# old_main_board.net
KiCad netlist of a schematic drawn in EAGLE
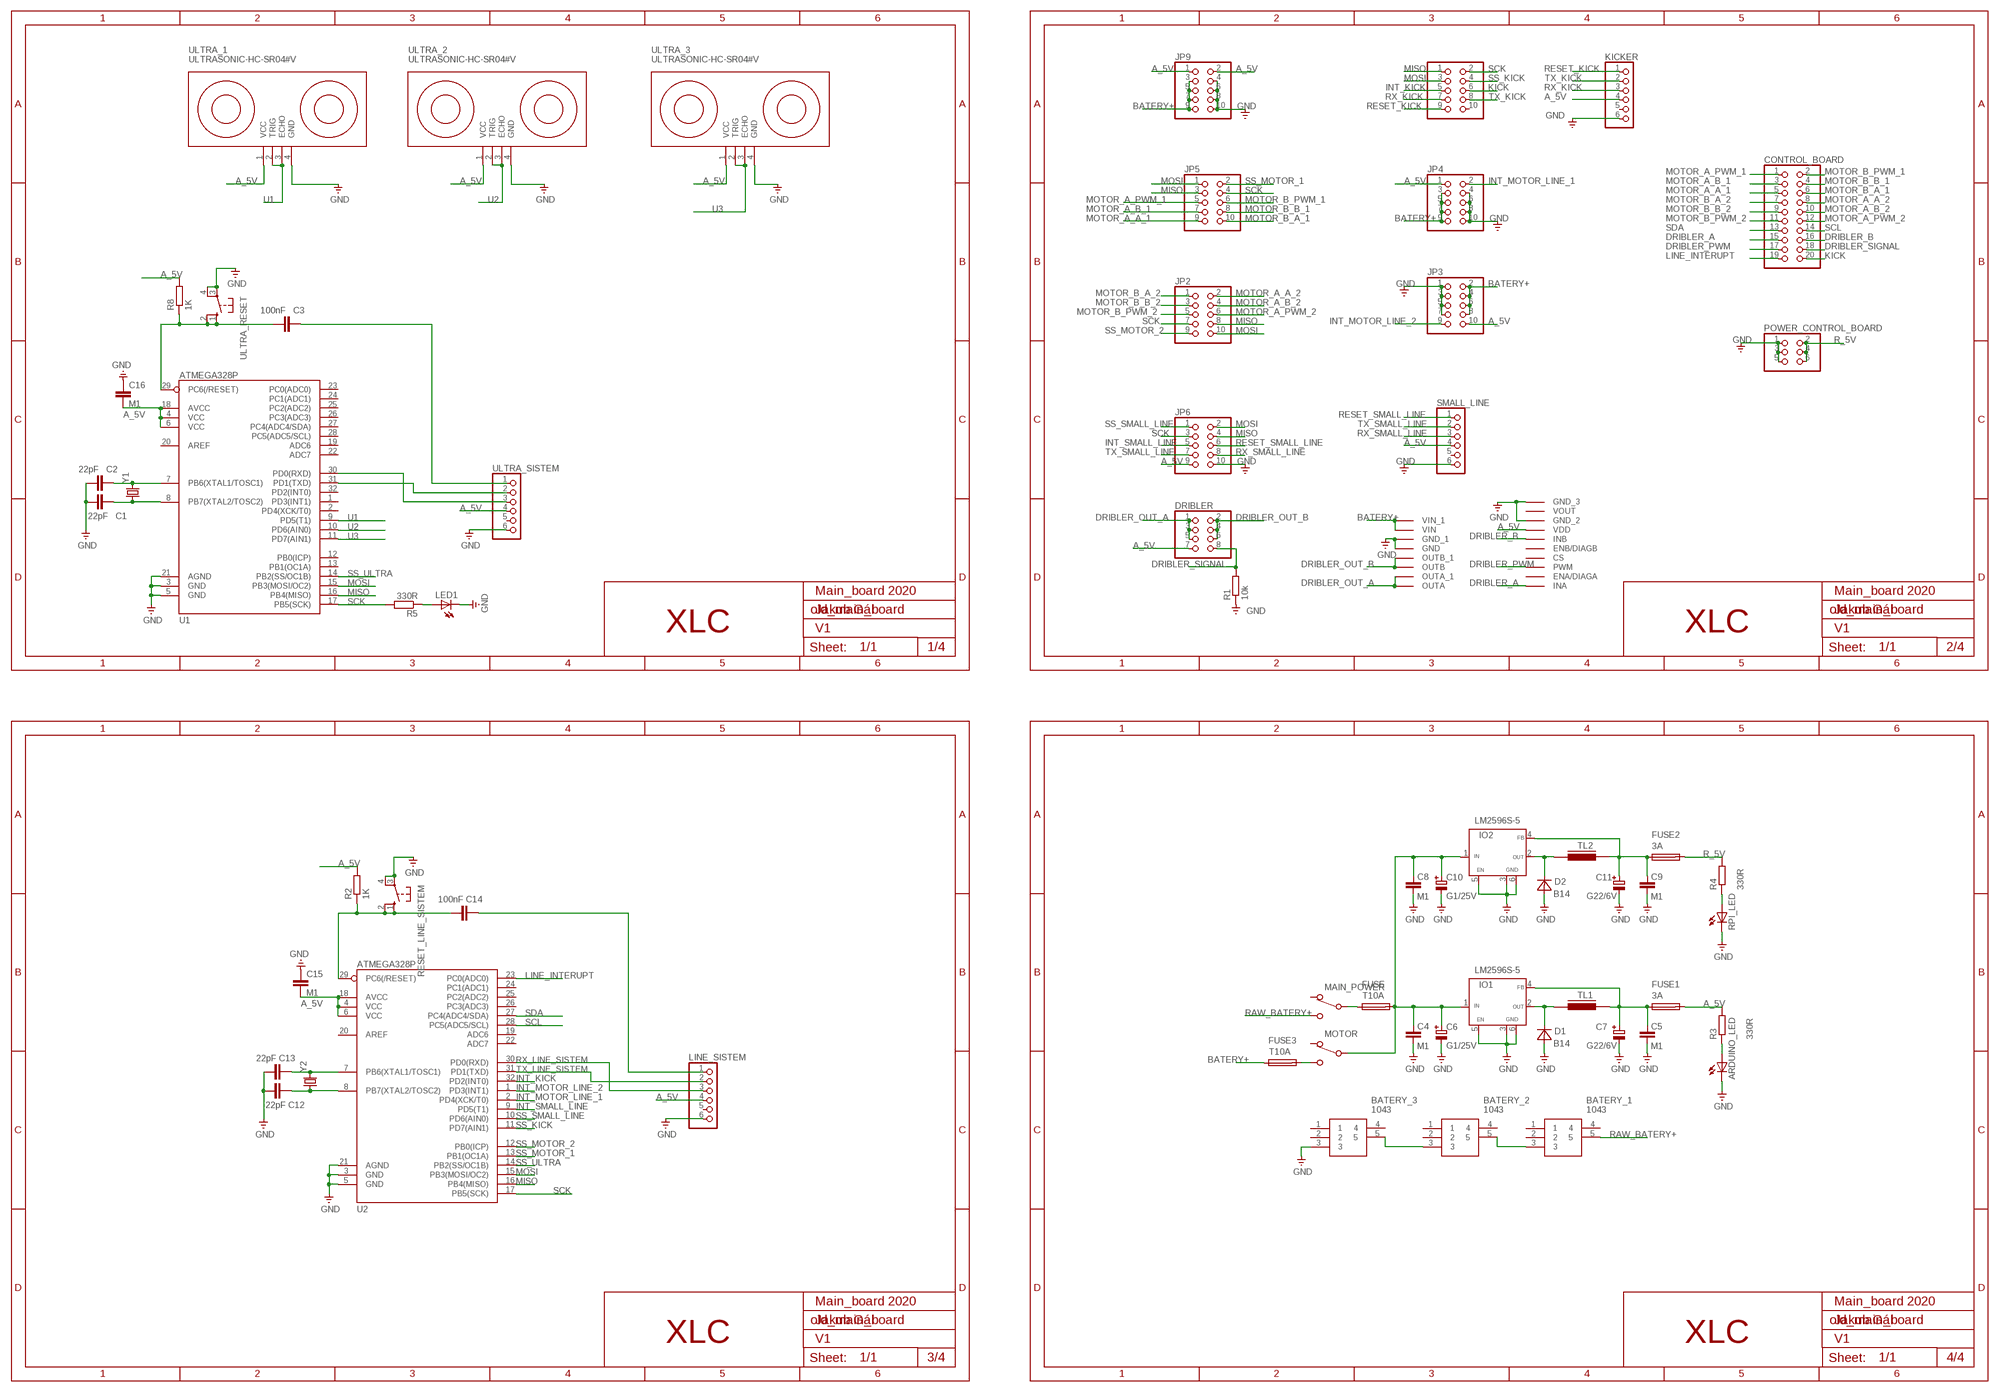
[diagram p0: schematic, sheet 1]

(export (version "E")
  (design (tool "Eeschema 10.0.6"))
  (components
    (comp (ref "ARDUINO_LED")
      (value "LEDCHIPLED_0603")
      (footprint "eagle-import:CHIPLED_0603")
      (libsource (lib "eagle-import") (part "LEDCHIPLED_0603"))
    )
    (comp (ref "BATERY_1")
      (value "1043")
      (footprint "eagle-import:1043")
      (fields (field (name "MOUSER_PART_NUMBER") "534-1043"))
      (libsource (lib "eagle-import") (part "1043"))
    )
    (comp (ref "BATERY_2")
      (value "1043")
      (footprint "eagle-import:1043")
      (fields (field (name "MOUSER_PART_NUMBER") "534-1043"))
      (libsource (lib "eagle-import") (part "1043"))
    )
    (comp (ref "BATERY_3")
      (value "1043")
      (footprint "eagle-import:1043")
      (fields (field (name "MOUSER_PART_NUMBER") "534-1043"))
      (libsource (lib "eagle-import") (part "1043"))
    )
    (comp (ref "C1")
      (value "22pF")
      (footprint "eagle-import:C0603")
      (libsource (lib "eagle-import") (part "rcl@1_C-EUC0603"))
    )
    (comp (ref "C2")
      (value "22pF")
      (footprint "eagle-import:C0603")
      (libsource (lib "eagle-import") (part "rcl@1_C-EUC0603"))
    )
    (comp (ref "C3")
      (value "100nF")
      (footprint "eagle-import:C0603")
      (libsource (lib "eagle-import") (part "rcl@1_C-EUC0603"))
    )
    (comp (ref "C4")
      (value "M1")
      (footprint "eagle-import:SMD-1206")
      (libsource (lib "eagle-import") (part "KOND-KERAM1206-SMD"))
    )
    (comp (ref "C5")
      (value "M1")
      (footprint "eagle-import:SMD-1206")
      (libsource (lib "eagle-import") (part "KOND-KERAM1206-SMD"))
    )
    (comp (ref "C6")
      (value "G1/25V")
      (footprint "eagle-import:SMD-ELE-D")
      (libsource (lib "eagle-import") (part "KOND-ELEKTD-SMD"))
    )
    (comp (ref "C7")
      (value "G22/6V")
      (footprint "eagle-import:SMD-ELE-D")
      (libsource (lib "eagle-import") (part "KOND-ELEKTD-SMD"))
    )
    (comp (ref "C8")
      (value "M1")
      (footprint "eagle-import:SMD-1206")
      (libsource (lib "eagle-import") (part "KOND-KERAM1206-SMD"))
    )
    (comp (ref "C9")
      (value "M1")
      (footprint "eagle-import:SMD-1206")
      (libsource (lib "eagle-import") (part "KOND-KERAM1206-SMD"))
    )
    (comp (ref "C10")
      (value "G1/25V")
      (footprint "eagle-import:SMD-ELE-D")
      (libsource (lib "eagle-import") (part "KOND-ELEKTD-SMD"))
    )
    (comp (ref "C11")
      (value "G22/6V")
      (footprint "eagle-import:SMD-ELE-D")
      (libsource (lib "eagle-import") (part "KOND-ELEKTD-SMD"))
    )
    (comp (ref "C12")
      (value "22pF")
      (footprint "eagle-import:C0603")
      (libsource (lib "eagle-import") (part "rcl@1_C-EUC0603"))
    )
    (comp (ref "C13")
      (value "22pF")
      (footprint "eagle-import:C0603")
      (libsource (lib "eagle-import") (part "rcl@1_C-EUC0603"))
    )
    (comp (ref "C14")
      (value "100nF")
      (footprint "eagle-import:C0603")
      (libsource (lib "eagle-import") (part "rcl@1_C-EUC0603"))
    )
    (comp (ref "C15")
      (value "M1")
      (footprint "eagle-import:C0603")
      (libsource (lib "eagle-import") (part "C-EUC0603"))
    )
    (comp (ref "C16")
      (value "M1")
      (footprint "eagle-import:C0603")
      (libsource (lib "eagle-import") (part "C-EUC0603"))
    )
    (comp (ref "CONTROL_BOARD")
      (value "PINHD-2X10_2.54-SMD")
      (footprint "eagle-import:2X10SMD")
      (libsource (lib "eagle-import") (part "PINHD-2X10_2.54-SMD"))
    )
    (comp (ref "D1")
      (value "B14")
      (footprint "eagle-import:D-3,6X5,5")
      (libsource (lib "eagle-import") (part "DIODASMD-3,6X5,5"))
    )
    (comp (ref "D2")
      (value "B14")
      (footprint "eagle-import:D-3,6X5,5")
      (libsource (lib "eagle-import") (part "DIODASMD-3,6X5,5"))
    )
    (comp (ref "DRIBLER")
      (value "PINHD-2X4_2.54-SMD")
      (footprint "eagle-import:2X04SMD")
      (libsource (lib "eagle-import") (part "PINHD-2X4_2.54-SMD"))
    )
    (comp (ref "FUSE")
      (value "T10A")
      (footprint "eagle-import:SH22,5A")
      (libsource (lib "eagle-import") (part "POISTKA2A"))
    )
    (comp (ref "FUSE1")
      (value "3A")
      (footprint "eagle-import:SH22,5A")
      (libsource (lib "eagle-import") (part "POISTKA2A"))
    )
    (comp (ref "FUSE2")
      (value "3A")
      (footprint "eagle-import:SH22,5A")
      (libsource (lib "eagle-import") (part "POISTKA2A"))
    )
    (comp (ref "FUSE3")
      (value "T10A")
      (footprint "eagle-import:SH22,5A")
      (libsource (lib "eagle-import") (part "POISTKA2A"))
    )
    (comp (ref "IO1")
      (value "LM2596S-5")
      (footprint "eagle-import:TO263-5")
      (libsource (lib "eagle-import") (part "LM2596S"))
    )
    (comp (ref "IO2")
      (value "LM2596S-5")
      (footprint "eagle-import:TO263-5")
      (libsource (lib "eagle-import") (part "LM2596S"))
    )
    (comp (ref "JP2")
      (value "PINHD-2X5_2.54-SMD")
      (footprint "eagle-import:2X05SMD")
      (libsource (lib "eagle-import") (part "PINHD-2X5_2.54-SMD"))
    )
    (comp (ref "JP3")
      (value "PINHD-2X5_2.54-SMD")
      (footprint "eagle-import:2X05SMD")
      (libsource (lib "eagle-import") (part "PINHD-2X5_2.54-SMD"))
    )
    (comp (ref "JP4")
      (value "PINHD-2X5_2.54-SMD")
      (footprint "eagle-import:2X05SMD")
      (libsource (lib "eagle-import") (part "PINHD-2X5_2.54-SMD"))
    )
    (comp (ref "JP5")
      (value "PINHD-2X5_2.54-SMD")
      (footprint "eagle-import:2X05SMD")
      (libsource (lib "eagle-import") (part "PINHD-2X5_2.54-SMD"))
    )
    (comp (ref "JP6")
      (value "PINHD-2X5_2.54-SMD")
      (footprint "eagle-import:2X05SMD")
      (libsource (lib "eagle-import") (part "PINHD-2X5_2.54-SMD"))
    )
    (comp (ref "JP8")
      (value "PINHD-2X5_2.54-SMD")
      (footprint "eagle-import:2X05SMD")
      (libsource (lib "eagle-import") (part "PINHD-2X5_2.54-SMD"))
    )
    (comp (ref "JP9")
      (value "PINHD-2X5_2.54-SMD")
      (footprint "eagle-import:2X05SMD")
      (libsource (lib "eagle-import") (part "PINHD-2X5_2.54-SMD"))
    )
    (comp (ref "KICKER")
      (value "PINHD-1X6")
      (footprint "eagle-import:1X06")
      (libsource (lib "eagle-import") (part "PINHD-1X6"))
    )
    (comp (ref "LED1")
      (value "LEDCHIPLED_0603")
      (footprint "eagle-import:CHIPLED_0603")
      (libsource (lib "eagle-import") (part "LEDCHIPLED_0603"))
    )
    (comp (ref "LINE_SISTEM")
      (value "PINHD-1X6")
      (footprint "eagle-import:1X06")
      (libsource (lib "eagle-import") (part "PINHD-1X6"))
    )
    (comp (ref "MAIN_POWER")
      (value "PREP-1PB")
      (footprint "eagle-import:P-B069B")
      (libsource (lib "eagle-import") (part "PREP-1PB"))
    )
    (comp (ref "MOTOR")
      (value "PREP-1PB")
      (footprint "eagle-import:P-B069B")
      (libsource (lib "eagle-import") (part "PREP-1PB"))
    )
    (comp (ref "POWER_CONTROL_BOARD")
      (value "PINHD-2X3_2.54-SMD")
      (footprint "eagle-import:2X03SMD")
      (libsource (lib "eagle-import") (part "PINHD-2X3_2.54-SMD"))
    )
    (comp (ref "R1")
      (value "10k")
      (footprint "eagle-import:R0603")
      (libsource (lib "eagle-import") (part "R-EU_R0603"))
    )
    (comp (ref "R2")
      (value "1K")
      (footprint "eagle-import:R0603")
      (libsource (lib "eagle-import") (part "R-EU_R0603"))
    )
    (comp (ref "R3")
      (value "330R")
      (footprint "eagle-import:R0603")
      (libsource (lib "eagle-import") (part "R-EU_R0603"))
    )
    (comp (ref "R4")
      (value "330R")
      (footprint "eagle-import:R0603")
      (libsource (lib "eagle-import") (part "R-EU_R0603"))
    )
    (comp (ref "R5")
      (value "330R")
      (footprint "eagle-import:R0603")
      (libsource (lib "eagle-import") (part "R-EU_R0603"))
    )
    (comp (ref "R8")
      (value "1K")
      (footprint "eagle-import:R0603")
      (libsource (lib "eagle-import") (part "R-EU_R0603"))
    )
    (comp (ref "RESET_LINE_SISTEM")
      (value "10-XX")
      (footprint "eagle-import:B3F-10XX")
      (fields (field (name "MPN") "B3F-1000"))
      (libsource (lib "eagle-import") (part "10-XX"))
    )
    (comp (ref "RPI_LED")
      (value "LEDCHIPLED_0603")
      (footprint "eagle-import:CHIPLED_0603")
      (libsource (lib "eagle-import") (part "LEDCHIPLED_0603"))
    )
    (comp (ref "SMALL_LINE")
      (value "PINHD-1X6")
      (footprint "eagle-import:1X06")
      (libsource (lib "eagle-import") (part "PINHD-1X6"))
    )
    (comp (ref "TL1")
      (value "INDUK-TLSMD1")
      (footprint "eagle-import:INDUK-TL")
      (libsource (lib "eagle-import") (part "INDUK-TLSMD1"))
    )
    (comp (ref "TL2")
      (value "INDUK-TLSMD1")
      (footprint "eagle-import:INDUK-TL")
      (libsource (lib "eagle-import") (part "INDUK-TLSMD1"))
    )
    (comp (ref "U$4")
      (value "MOTOR_DRIVER")
      (footprint "eagle-import:MOTOR_DRIVER")
      (libsource (lib "eagle-import") (part "MOTOR_DRIVER"))
    )
    (comp (ref "U1")
      (value "ATMEGA328P")
      (footprint "eagle-import:TQFP32-08")
      (libsource (lib "eagle-import") (part "ATMEGA328_SMT"))
    )
    (comp (ref "U2")
      (value "ATMEGA328P")
      (footprint "eagle-import:TQFP32-08")
      (libsource (lib "eagle-import") (part "ATMEGA328_SMT"))
    )
    (comp (ref "ULTRA_1")
      (value "ULTRASONIC-HC-SR04#V")
      (footprint "eagle-import:ULTRASONIC-HC-SR04#V")
      (libsource (lib "eagle-import") (part "ULTRASONIC-HC-SR04#V"))
    )
    (comp (ref "ULTRA_2")
      (value "ULTRASONIC-HC-SR04#V")
      (footprint "eagle-import:ULTRASONIC-HC-SR04#V")
      (libsource (lib "eagle-import") (part "ULTRASONIC-HC-SR04#V"))
    )
    (comp (ref "ULTRA_3")
      (value "ULTRASONIC-HC-SR04#V")
      (footprint "eagle-import:ULTRASONIC-HC-SR04#V")
      (libsource (lib "eagle-import") (part "ULTRASONIC-HC-SR04#V"))
    )
    (comp (ref "ULTRA_RESET")
      (value "10-XX")
      (footprint "eagle-import:B3F-10XX")
      (fields (field (name "MPN") "B3F-1000"))
      (libsource (lib "eagle-import") (part "10-XX"))
    )
    (comp (ref "ULTRA_SISTEM")
      (value "PINHD-1X6")
      (footprint "eagle-import:1X06")
      (libsource (lib "eagle-import") (part "PINHD-1X6"))
    )
    (comp (ref "Y1")
      (value "CRYSTALHC49US")
      (footprint "eagle-import:HC49US")
      (libsource (lib "eagle-import") (part "CRYSTALHC49US"))
    )
    (comp (ref "Y2")
      (value "CRYSTALHC49US")
      (footprint "eagle-import:HC49US")
      (libsource (lib "eagle-import") (part "CRYSTALHC49US"))
    )
  )
  (nets
    (net (code "1") (name "/A_5V") (class "Default")
      (node (ref "C15") (pin "2") (pinfunction "2_2") (pintype "passive"))
      (node (ref "C16") (pin "2") (pinfunction "2_2") (pintype "passive"))
      (node (ref "DRIBLER") (pin "7") (pinfunction "7_7") (pintype "passive"))
      (node (ref "FUSE1") (pin "2") (pinfunction "2_2") (pintype "passive"))
      (node (ref "JP3") (pin "10") (pinfunction "10_10") (pintype "passive"))
      (node (ref "JP4") (pin "1") (pinfunction "1_1") (pintype "passive"))
      (node (ref "JP6") (pin "9") (pinfunction "9_9") (pintype "passive"))
      (node (ref "JP9") (pin "1") (pinfunction "1_1") (pintype "passive"))
      (node (ref "JP9") (pin "2") (pinfunction "2_2") (pintype "passive"))
      (node (ref "KICKER") (pin "4") (pinfunction "4_4") (pintype "passive"))
      (node (ref "LINE_SISTEM") (pin "4") (pinfunction "4_4") (pintype "passive"))
      (node (ref "R2") (pin "2") (pinfunction "2_2") (pintype "passive"))
      (node (ref "R3") (pin "2") (pinfunction "2_2") (pintype "passive"))
      (node (ref "R8") (pin "2") (pinfunction "2_2") (pintype "passive"))
      (node (ref "SMALL_LINE") (pin "4") (pinfunction "4_4") (pintype "passive"))
      (node (ref "U$4") (pin "VDD") (pinfunction "VDD_VDD") (pintype "bidirectional"))
      (node (ref "U1") (pin "18") (pinfunction "AVCC_18") (pintype "bidirectional"))
      (node (ref "U1") (pin "4") (pinfunction "VCC_4") (pintype "bidirectional"))
      (node (ref "U1") (pin "6") (pinfunction "VCC_6") (pintype "bidirectional"))
      (node (ref "U2") (pin "18") (pinfunction "AVCC_18") (pintype "bidirectional"))
      (node (ref "U2") (pin "4") (pinfunction "VCC_4") (pintype "bidirectional"))
      (node (ref "U2") (pin "6") (pinfunction "VCC_6") (pintype "bidirectional"))
      (node (ref "ULTRA_1") (pin "1") (pinfunction "VCC_1") (pintype "power_in"))
      (node (ref "ULTRA_2") (pin "1") (pinfunction "VCC_1") (pintype "power_in"))
      (node (ref "ULTRA_3") (pin "1") (pinfunction "VCC_1") (pintype "power_in"))
      (node (ref "ULTRA_SISTEM") (pin "4") (pinfunction "4_4") (pintype "passive"))
    )
    (net (code "2") (name "/BATERY+") (class "Default")
      (node (ref "FUSE3") (pin "1") (pinfunction "1_1") (pintype "passive"))
      (node (ref "JP3") (pin "2") (pinfunction "2_2") (pintype "passive"))
      (node (ref "JP3") (pin "4") (pinfunction "4_4") (pintype "passive"))
      (node (ref "JP3") (pin "6") (pinfunction "6_6") (pintype "passive"))
      (node (ref "JP3") (pin "8") (pinfunction "8_8") (pintype "passive"))
      (node (ref "JP4") (pin "3") (pinfunction "3_3") (pintype "passive"))
      (node (ref "JP4") (pin "5") (pinfunction "5_5") (pintype "passive"))
      (node (ref "JP4") (pin "7") (pinfunction "7_7") (pintype "passive"))
      (node (ref "JP4") (pin "9") (pinfunction "9_9") (pintype "passive"))
      (node (ref "JP9") (pin "3") (pinfunction "3_3") (pintype "passive"))
      (node (ref "JP9") (pin "5") (pinfunction "5_5") (pintype "passive"))
      (node (ref "JP9") (pin "7") (pinfunction "7_7") (pintype "passive"))
      (node (ref "JP9") (pin "9") (pinfunction "9_9") (pintype "passive"))
      (node (ref "U$4") (pin "VIN") (pinfunction "VIN_VIN") (pintype "bidirectional"))
      (node (ref "U$4") (pin "VIN_1") (pinfunction "VIN_1_VIN_1") (pintype "bidirectional"))
    )
    (net (code "3") (name "/DRIBLER_A") (class "Default")
      (node (ref "CONTROL_BOARD") (pin "15") (pinfunction "15_15") (pintype "passive"))
      (node (ref "U$4") (pin "INA") (pinfunction "INA_INA") (pintype "bidirectional"))
    )
    (net (code "4") (name "/DRIBLER_B") (class "Default")
      (node (ref "CONTROL_BOARD") (pin "16") (pinfunction "16_16") (pintype "passive"))
      (node (ref "U$4") (pin "INB") (pinfunction "INB_INB") (pintype "bidirectional"))
    )
    (net (code "5") (name "/DRIBLER_OUT_A") (class "Default")
      (node (ref "DRIBLER") (pin "1") (pinfunction "1_1") (pintype "passive"))
      (node (ref "DRIBLER") (pin "3") (pinfunction "3_3") (pintype "passive"))
      (node (ref "DRIBLER") (pin "5") (pinfunction "5_5") (pintype "passive"))
      (node (ref "U$4") (pin "OUTA") (pinfunction "OUTA_OUTA") (pintype "bidirectional"))
      (node (ref "U$4") (pin "OUTA_1") (pinfunction "OUTA_1_OUTA_1") (pintype "bidirectional"))
    )
    (net (code "6") (name "/DRIBLER_OUT_B") (class "Default")
      (node (ref "DRIBLER") (pin "2") (pinfunction "2_2") (pintype "passive"))
      (node (ref "DRIBLER") (pin "4") (pinfunction "4_4") (pintype "passive"))
      (node (ref "DRIBLER") (pin "6") (pinfunction "6_6") (pintype "passive"))
      (node (ref "U$4") (pin "OUTB") (pinfunction "OUTB_OUTB") (pintype "bidirectional"))
      (node (ref "U$4") (pin "OUTB_1") (pinfunction "OUTB_1_OUTB_1") (pintype "bidirectional"))
    )
    (net (code "7") (name "/DRIBLER_PWM") (class "Default")
      (node (ref "CONTROL_BOARD") (pin "17") (pinfunction "17_17") (pintype "passive"))
      (node (ref "U$4") (pin "PWM") (pinfunction "PWM_PWM") (pintype "bidirectional"))
    )
    (net (code "8") (name "/DRIBLER_SIGNAL") (class "Default")
      (node (ref "CONTROL_BOARD") (pin "18") (pinfunction "18_18") (pintype "passive"))
      (node (ref "DRIBLER") (pin "8") (pinfunction "8_8") (pintype "passive"))
      (node (ref "R1") (pin "2") (pinfunction "2_2") (pintype "passive"))
    )
    (net (code "9") (name "/INT_KICK") (class "Default")
      (node (ref "JP8") (pin "5") (pinfunction "5_5") (pintype "passive"))
      (node (ref "U2") (pin "32") (pinfunction "PD2(INT0)_32") (pintype "bidirectional"))
    )
    (net (code "10") (name "/INT_MOTOR_LINE_1") (class "Default")
      (node (ref "JP4") (pin "2") (pinfunction "2_2") (pintype "passive"))
      (node (ref "U2") (pin "2") (pinfunction "PD4(XCK/T0)_2") (pintype "bidirectional"))
    )
    (net (code "11") (name "/INT_MOTOR_LINE_2") (class "Default")
      (node (ref "JP3") (pin "9") (pinfunction "9_9") (pintype "passive"))
      (node (ref "U2") (pin "1") (pinfunction "PD3(INT1)_1") (pintype "bidirectional"))
    )
    (net (code "12") (name "/INT_SMALL_LINE") (class "Default")
      (node (ref "JP6") (pin "5") (pinfunction "5_5") (pintype "passive"))
      (node (ref "U2") (pin "9") (pinfunction "PD5(T1)_9") (pintype "bidirectional"))
    )
    (net (code "13") (name "/KICK") (class "Default")
      (node (ref "CONTROL_BOARD") (pin "20") (pinfunction "20_20") (pintype "passive"))
      (node (ref "JP8") (pin "6") (pinfunction "6_6") (pintype "passive"))
    )
    (net (code "14") (name "/LINE_INTERUPT") (class "Default")
      (node (ref "CONTROL_BOARD") (pin "19") (pinfunction "19_19") (pintype "passive"))
      (node (ref "U2") (pin "23") (pinfunction "PC0(ADC0)_23") (pintype "bidirectional"))
    )
    (net (code "15") (name "/MISO") (class "Default")
      (node (ref "JP2") (pin "8") (pinfunction "8_8") (pintype "passive"))
      (node (ref "JP5") (pin "3") (pinfunction "3_3") (pintype "passive"))
      (node (ref "JP6") (pin "4") (pinfunction "4_4") (pintype "passive"))
      (node (ref "JP8") (pin "1") (pinfunction "1_1") (pintype "passive"))
      (node (ref "U1") (pin "16") (pinfunction "PB4(MISO)_16") (pintype "bidirectional"))
      (node (ref "U2") (pin "16") (pinfunction "PB4(MISO)_16") (pintype "bidirectional"))
    )
    (net (code "16") (name "/MOSI") (class "Default")
      (node (ref "JP2") (pin "10") (pinfunction "10_10") (pintype "passive"))
      (node (ref "JP5") (pin "1") (pinfunction "1_1") (pintype "passive"))
      (node (ref "JP6") (pin "2") (pinfunction "2_2") (pintype "passive"))
      (node (ref "JP8") (pin "3") (pinfunction "3_3") (pintype "passive"))
      (node (ref "U1") (pin "15") (pinfunction "PB3(MOSI/OC2)_15") (pintype "bidirectional"))
      (node (ref "U2") (pin "15") (pinfunction "PB3(MOSI/OC2)_15") (pintype "bidirectional"))
    )
    (net (code "17") (name "/MOTOR_A_A_1") (class "Default")
      (node (ref "CONTROL_BOARD") (pin "5") (pinfunction "5_5") (pintype "passive"))
      (node (ref "JP5") (pin "9") (pinfunction "9_9") (pintype "passive"))
    )
    (net (code "18") (name "/MOTOR_A_A_2") (class "Default")
      (node (ref "CONTROL_BOARD") (pin "8") (pinfunction "8_8") (pintype "passive"))
      (node (ref "JP2") (pin "2") (pinfunction "2_2") (pintype "passive"))
    )
    (net (code "19") (name "/MOTOR_A_B_1") (class "Default")
      (node (ref "CONTROL_BOARD") (pin "3") (pinfunction "3_3") (pintype "passive"))
      (node (ref "JP5") (pin "7") (pinfunction "7_7") (pintype "passive"))
    )
    (net (code "20") (name "/MOTOR_A_B_2") (class "Default")
      (node (ref "CONTROL_BOARD") (pin "10") (pinfunction "10_10") (pintype "passive"))
      (node (ref "JP2") (pin "4") (pinfunction "4_4") (pintype "passive"))
    )
    (net (code "21") (name "/MOTOR_A_PWM_1") (class "Default")
      (node (ref "CONTROL_BOARD") (pin "1") (pinfunction "1_1") (pintype "passive"))
      (node (ref "JP5") (pin "5") (pinfunction "5_5") (pintype "passive"))
    )
    (net (code "22") (name "/MOTOR_A_PWM_2") (class "Default")
      (node (ref "CONTROL_BOARD") (pin "12") (pinfunction "12_12") (pintype "passive"))
      (node (ref "JP2") (pin "6") (pinfunction "6_6") (pintype "passive"))
    )
    (net (code "23") (name "/MOTOR_B_A_1") (class "Default")
      (node (ref "CONTROL_BOARD") (pin "6") (pinfunction "6_6") (pintype "passive"))
      (node (ref "JP5") (pin "10") (pinfunction "10_10") (pintype "passive"))
    )
    (net (code "24") (name "/MOTOR_B_A_2") (class "Default")
      (node (ref "CONTROL_BOARD") (pin "7") (pinfunction "7_7") (pintype "passive"))
      (node (ref "JP2") (pin "1") (pinfunction "1_1") (pintype "passive"))
    )
    (net (code "25") (name "/MOTOR_B_B_1") (class "Default")
      (node (ref "CONTROL_BOARD") (pin "4") (pinfunction "4_4") (pintype "passive"))
      (node (ref "JP5") (pin "8") (pinfunction "8_8") (pintype "passive"))
    )
    (net (code "26") (name "/MOTOR_B_B_2") (class "Default")
      (node (ref "CONTROL_BOARD") (pin "9") (pinfunction "9_9") (pintype "passive"))
      (node (ref "JP2") (pin "3") (pinfunction "3_3") (pintype "passive"))
    )
    (net (code "27") (name "/MOTOR_B_PWM_1") (class "Default")
      (node (ref "CONTROL_BOARD") (pin "2") (pinfunction "2_2") (pintype "passive"))
      (node (ref "JP5") (pin "6") (pinfunction "6_6") (pintype "passive"))
    )
    (net (code "28") (name "/MOTOR_B_PWM_2") (class "Default")
      (node (ref "CONTROL_BOARD") (pin "11") (pinfunction "11_11") (pintype "passive"))
      (node (ref "JP2") (pin "5") (pinfunction "5_5") (pintype "passive"))
    )
    (net (code "29") (name "/RAW_BATERY+") (class "Default")
      (node (ref "BATERY_1") (pin "5") (pinfunction "5_5") (pintype "bidirectional"))
      (node (ref "MAIN_POWER") (pin "1") (pinfunction "1-OFF_1") (pintype "passive"))
    )
    (net (code "30") (name "/RESET_KICK") (class "Default")
      (node (ref "JP8") (pin "9") (pinfunction "9_9") (pintype "passive"))
      (node (ref "KICKER") (pin "1") (pinfunction "1_1") (pintype "passive"))
    )
    (net (code "31") (name "/RESET_SMALL_LINE") (class "Default")
      (node (ref "JP6") (pin "6") (pinfunction "6_6") (pintype "passive"))
      (node (ref "SMALL_LINE") (pin "1") (pinfunction "1_1") (pintype "passive"))
    )
    (net (code "32") (name "/RX_KICK") (class "Default")
      (node (ref "JP8") (pin "7") (pinfunction "7_7") (pintype "passive"))
      (node (ref "KICKER") (pin "3") (pinfunction "3_3") (pintype "passive"))
    )
    (net (code "33") (name "/RX_LINE_SISTEM") (class "Default")
      (node (ref "LINE_SISTEM") (pin "3") (pinfunction "3_3") (pintype "passive"))
      (node (ref "U2") (pin "30") (pinfunction "PD0(RXD)_30") (pintype "bidirectional"))
    )
    (net (code "34") (name "/RX_SMALL_LINE") (class "Default")
      (node (ref "JP6") (pin "8") (pinfunction "8_8") (pintype "passive"))
      (node (ref "SMALL_LINE") (pin "3") (pinfunction "3_3") (pintype "passive"))
    )
    (net (code "35") (name "/R_5V") (class "Default")
      (node (ref "FUSE2") (pin "2") (pinfunction "2_2") (pintype "passive"))
      (node (ref "POWER_CONTROL_BOARD") (pin "2") (pinfunction "2_2") (pintype "passive"))
      (node (ref "POWER_CONTROL_BOARD") (pin "4") (pinfunction "4_4") (pintype "passive"))
      (node (ref "POWER_CONTROL_BOARD") (pin "6") (pinfunction "6_6") (pintype "passive"))
      (node (ref "R4") (pin "2") (pinfunction "2_2") (pintype "passive"))
    )
    (net (code "36") (name "/SCK") (class "Default")
      (node (ref "JP2") (pin "7") (pinfunction "7_7") (pintype "passive"))
      (node (ref "JP5") (pin "4") (pinfunction "4_4") (pintype "passive"))
      (node (ref "JP6") (pin "3") (pinfunction "3_3") (pintype "passive"))
      (node (ref "JP8") (pin "2") (pinfunction "2_2") (pintype "passive"))
      (node (ref "R5") (pin "2") (pinfunction "2_2") (pintype "passive"))
      (node (ref "U1") (pin "17") (pinfunction "PB5(SCK)_17") (pintype "bidirectional"))
      (node (ref "U2") (pin "17") (pinfunction "PB5(SCK)_17") (pintype "bidirectional"))
    )
    (net (code "37") (name "/SCL") (class "Default")
      (node (ref "CONTROL_BOARD") (pin "14") (pinfunction "14_14") (pintype "passive"))
      (node (ref "U2") (pin "28") (pinfunction "PC5(ADC5/SCL)_28") (pintype "bidirectional"))
    )
    (net (code "38") (name "/SDA") (class "Default")
      (node (ref "CONTROL_BOARD") (pin "13") (pinfunction "13_13") (pintype "passive"))
      (node (ref "U2") (pin "27") (pinfunction "PC4(ADC4/SDA)_27") (pintype "bidirectional"))
    )
    (net (code "39") (name "/SS_KICK") (class "Default")
      (node (ref "JP8") (pin "4") (pinfunction "4_4") (pintype "passive"))
      (node (ref "U2") (pin "11") (pinfunction "PD7(AIN1)_11") (pintype "bidirectional"))
    )
    (net (code "40") (name "/SS_MOTOR_1") (class "Default")
      (node (ref "JP5") (pin "2") (pinfunction "2_2") (pintype "passive"))
      (node (ref "U2") (pin "13") (pinfunction "PB1(OC1A)_13") (pintype "bidirectional"))
    )
    (net (code "41") (name "/SS_MOTOR_2") (class "Default")
      (node (ref "JP2") (pin "9") (pinfunction "9_9") (pintype "passive"))
      (node (ref "U2") (pin "12") (pinfunction "PB0(ICP)_12") (pintype "bidirectional"))
    )
    (net (code "42") (name "/SS_SMALL_LINE") (class "Default")
      (node (ref "JP6") (pin "1") (pinfunction "1_1") (pintype "passive"))
      (node (ref "U2") (pin "10") (pinfunction "PD6(AIN0)_10") (pintype "bidirectional"))
    )
    (net (code "43") (name "/SS_ULTRA") (class "Default")
      (node (ref "U1") (pin "14") (pinfunction "PB2(SS/OC1B)_14") (pintype "bidirectional"))
      (node (ref "U2") (pin "14") (pinfunction "PB2(SS/OC1B)_14") (pintype "bidirectional"))
    )
    (net (code "44") (name "/TX_KICK") (class "Default")
      (node (ref "JP8") (pin "8") (pinfunction "8_8") (pintype "passive"))
      (node (ref "KICKER") (pin "2") (pinfunction "2_2") (pintype "passive"))
    )
    (net (code "45") (name "/TX_LINE_SISTEM") (class "Default")
      (node (ref "LINE_SISTEM") (pin "2") (pinfunction "2_2") (pintype "passive"))
      (node (ref "U2") (pin "31") (pinfunction "PD1(TXD)_31") (pintype "bidirectional"))
    )
    (net (code "46") (name "/TX_SMALL_LINE") (class "Default")
      (node (ref "JP6") (pin "7") (pinfunction "7_7") (pintype "passive"))
      (node (ref "SMALL_LINE") (pin "2") (pinfunction "2_2") (pintype "passive"))
    )
    (net (code "47") (name "/U1") (class "Default")
      (node (ref "U1") (pin "9") (pinfunction "PD5(T1)_9") (pintype "bidirectional"))
      (node (ref "ULTRA_1") (pin "2") (pinfunction "TRIG_2") (pintype "input"))
      (node (ref "ULTRA_1") (pin "3") (pinfunction "ECHO_3") (pintype "output"))
    )
    (net (code "48") (name "/U2") (class "Default")
      (node (ref "U1") (pin "10") (pinfunction "PD6(AIN0)_10") (pintype "bidirectional"))
      (node (ref "ULTRA_2") (pin "2") (pinfunction "TRIG_2") (pintype "input"))
      (node (ref "ULTRA_2") (pin "3") (pinfunction "ECHO_3") (pintype "output"))
    )
    (net (code "49") (name "/U3") (class "Default")
      (node (ref "U1") (pin "11") (pinfunction "PD7(AIN1)_11") (pintype "bidirectional"))
      (node (ref "ULTRA_3") (pin "2") (pinfunction "TRIG_2") (pintype "input"))
      (node (ref "ULTRA_3") (pin "3") (pinfunction "ECHO_3") (pintype "output"))
    )
    (net (code "50") (name "GND") (class "Default")
      (node (ref "ARDUINO_LED") (pin "C") (pinfunction "C_C") (pintype "passive"))
      (node (ref "BATERY_3") (pin "3") (pinfunction "3_3") (pintype "bidirectional"))
      (node (ref "C1") (pin "1") (pinfunction "1_1") (pintype "passive"))
      (node (ref "C10") (pin "MINUS") (pinfunction "MINUS_MINUS") (pintype "passive"))
      (node (ref "C11") (pin "MINUS") (pinfunction "MINUS_MINUS") (pintype "passive"))
      (node (ref "C12") (pin "1") (pinfunction "1_1") (pintype "passive"))
      (node (ref "C13") (pin "1") (pinfunction "1_1") (pintype "passive"))
      (node (ref "C15") (pin "1") (pinfunction "1_1") (pintype "passive"))
      (node (ref "C16") (pin "1") (pinfunction "1_1") (pintype "passive"))
      (node (ref "C2") (pin "1") (pinfunction "1_1") (pintype "passive"))
      (node (ref "C4") (pin "1") (pinfunction "1_1") (pintype "passive"))
      (node (ref "C5") (pin "1") (pinfunction "1_1") (pintype "passive"))
      (node (ref "C6") (pin "MINUS") (pinfunction "MINUS_MINUS") (pintype "passive"))
      (node (ref "C7") (pin "MINUS") (pinfunction "MINUS_MINUS") (pintype "passive"))
      (node (ref "C8") (pin "1") (pinfunction "1_1") (pintype "passive"))
      (node (ref "C9") (pin "1") (pinfunction "1_1") (pintype "passive"))
      (node (ref "D1") (pin "A") (pinfunction "A_A") (pintype "passive"))
      (node (ref "D2") (pin "A") (pinfunction "A_A") (pintype "passive"))
      (node (ref "IO1") (pin "3") (pinfunction "GND_3") (pintype "power_in"))
      (node (ref "IO1") (pin "5") (pinfunction "EN_5") (pintype "input"))
      (node (ref "IO1") (pin "6") (pinfunction "GND_6") (pintype "power_in"))
      (node (ref "IO2") (pin "3") (pinfunction "GND_3") (pintype "power_in"))
      (node (ref "IO2") (pin "5") (pinfunction "EN_5") (pintype "input"))
      (node (ref "IO2") (pin "6") (pinfunction "GND_6") (pintype "power_in"))
      (node (ref "JP3") (pin "1") (pinfunction "1_1") (pintype "passive"))
      (node (ref "JP3") (pin "3") (pinfunction "3_3") (pintype "passive"))
      (node (ref "JP3") (pin "5") (pinfunction "5_5") (pintype "passive"))
      (node (ref "JP3") (pin "7") (pinfunction "7_7") (pintype "passive"))
      (node (ref "JP4") (pin "10") (pinfunction "10_10") (pintype "passive"))
      (node (ref "JP4") (pin "4") (pinfunction "4_4") (pintype "passive"))
      (node (ref "JP4") (pin "6") (pinfunction "6_6") (pintype "passive"))
      (node (ref "JP4") (pin "8") (pinfunction "8_8") (pintype "passive"))
      (node (ref "JP6") (pin "10") (pinfunction "10_10") (pintype "passive"))
      (node (ref "JP9") (pin "10") (pinfunction "10_10") (pintype "passive"))
      (node (ref "JP9") (pin "4") (pinfunction "4_4") (pintype "passive"))
      (node (ref "JP9") (pin "6") (pinfunction "6_6") (pintype "passive"))
      (node (ref "JP9") (pin "8") (pinfunction "8_8") (pintype "passive"))
      (node (ref "KICKER") (pin "6") (pinfunction "6_6") (pintype "passive"))
      (node (ref "LED1") (pin "C") (pinfunction "C_C") (pintype "passive"))
      (node (ref "LINE_SISTEM") (pin "6") (pinfunction "6_6") (pintype "passive"))
      (node (ref "POWER_CONTROL_BOARD") (pin "1") (pinfunction "1_1") (pintype "passive"))
      (node (ref "POWER_CONTROL_BOARD") (pin "3") (pinfunction "3_3") (pintype "passive"))
      (node (ref "POWER_CONTROL_BOARD") (pin "5") (pinfunction "5_5") (pintype "passive"))
      (node (ref "R1") (pin "1") (pinfunction "1_1") (pintype "passive"))
      (node (ref "RESET_LINE_SISTEM") (pin "3") (pinfunction "P_3") (pintype "passive"))
      (node (ref "RESET_LINE_SISTEM") (pin "4") (pinfunction "P1_4") (pintype "passive"))
      (node (ref "RPI_LED") (pin "C") (pinfunction "C_C") (pintype "passive"))
      (node (ref "SMALL_LINE") (pin "6") (pinfunction "6_6") (pintype "passive"))
      (node (ref "U$4") (pin "GND") (pinfunction "GND_GND") (pintype "bidirectional"))
      (node (ref "U$4") (pin "GND_1") (pinfunction "GND_1_GND_1") (pintype "bidirectional"))
      (node (ref "U$4") (pin "GND_2") (pinfunction "GND_2_GND_2") (pintype "bidirectional"))
      (node (ref "U$4") (pin "GND_3") (pinfunction "GND_3_GND_3") (pintype "bidirectional"))
      (node (ref "U1") (pin "21") (pinfunction "AGND_21") (pintype "bidirectional"))
      (node (ref "U1") (pin "3") (pinfunction "GND_3") (pintype "bidirectional"))
      (node (ref "U1") (pin "5") (pinfunction "GND_5") (pintype "bidirectional"))
      (node (ref "U2") (pin "21") (pinfunction "AGND_21") (pintype "bidirectional"))
      (node (ref "U2") (pin "3") (pinfunction "GND_3") (pintype "bidirectional"))
      (node (ref "U2") (pin "5") (pinfunction "GND_5") (pintype "bidirectional"))
      (node (ref "ULTRA_1") (pin "4") (pinfunction "GND_4") (pintype "power_in"))
      (node (ref "ULTRA_2") (pin "4") (pinfunction "GND_4") (pintype "power_in"))
      (node (ref "ULTRA_3") (pin "4") (pinfunction "GND_4") (pintype "power_in"))
      (node (ref "ULTRA_RESET") (pin "3") (pinfunction "P_3") (pintype "passive"))
      (node (ref "ULTRA_RESET") (pin "4") (pinfunction "P1_4") (pintype "passive"))
      (node (ref "ULTRA_SISTEM") (pin "6") (pinfunction "6_6") (pintype "passive"))
    )
    (net (code "51") (name "Net-(ARDUINO_LED-PadA)") (class "Default")
      (node (ref "ARDUINO_LED") (pin "A") (pinfunction "A_A") (pintype "passive"))
      (node (ref "R3") (pin "1") (pinfunction "1_1") (pintype "passive"))
    )
    (net (code "52") (name "Net-(BATERY_1-Pad3)") (class "Default")
      (node (ref "BATERY_1") (pin "3") (pinfunction "3_3") (pintype "bidirectional"))
      (node (ref "BATERY_2") (pin "5") (pinfunction "5_5") (pintype "bidirectional"))
    )
    (net (code "53") (name "Net-(BATERY_2-Pad3)") (class "Default")
      (node (ref "BATERY_2") (pin "3") (pinfunction "3_3") (pintype "bidirectional"))
      (node (ref "BATERY_3") (pin "5") (pinfunction "5_5") (pintype "bidirectional"))
    )
    (net (code "54") (name "Net-(C3-Pad2)") (class "Default")
      (node (ref "C3") (pin "2") (pinfunction "2_2") (pintype "passive"))
      (node (ref "ULTRA_SISTEM") (pin "1") (pinfunction "1_1") (pintype "passive"))
    )
    (net (code "55") (name "Net-(C14-Pad2)") (class "Default")
      (node (ref "C14") (pin "2") (pinfunction "2_2") (pintype "passive"))
      (node (ref "LINE_SISTEM") (pin "1") (pinfunction "1_1") (pintype "passive"))
    )
    (net (code "56") (name "Net-(IO1-FB)") (class "Default")
      (node (ref "C5") (pin "2") (pinfunction "2_2") (pintype "passive"))
      (node (ref "C7") (pin "PLUS") (pinfunction "PLUS_PLUS") (pintype "passive"))
      (node (ref "FUSE1") (pin "1") (pinfunction "1_1") (pintype "passive"))
      (node (ref "IO1") (pin "4") (pinfunction "FB_4") (pintype "input"))
      (node (ref "TL1") (pin "2") (pinfunction "2_2") (pintype "passive"))
    )
    (net (code "57") (name "Net-(IO1-IN)") (class "Default")
      (node (ref "C10") (pin "PLUS") (pinfunction "PLUS_PLUS") (pintype "passive"))
      (node (ref "C4") (pin "2") (pinfunction "2_2") (pintype "passive"))
      (node (ref "C6") (pin "PLUS") (pinfunction "PLUS_PLUS") (pintype "passive"))
      (node (ref "C8") (pin "2") (pinfunction "2_2") (pintype "passive"))
      (node (ref "FUSE") (pin "2") (pinfunction "2_2") (pintype "passive"))
      (node (ref "IO1") (pin "1") (pinfunction "IN_1") (pintype "input"))
      (node (ref "IO2") (pin "1") (pinfunction "IN_1") (pintype "input"))
      (node (ref "MOTOR") (pin "2") (pinfunction "2-COM_2") (pintype "passive"))
    )
    (net (code "58") (name "Net-(IO1-OUT)") (class "Default")
      (node (ref "D1") (pin "K") (pinfunction "K_K") (pintype "passive"))
      (node (ref "IO1") (pin "2") (pinfunction "OUT_2") (pintype "output"))
      (node (ref "TL1") (pin "1") (pinfunction "1_1") (pintype "passive"))
    )
    (net (code "59") (name "Net-(IO2-FB)") (class "Default")
      (node (ref "C11") (pin "PLUS") (pinfunction "PLUS_PLUS") (pintype "passive"))
      (node (ref "C9") (pin "2") (pinfunction "2_2") (pintype "passive"))
      (node (ref "FUSE2") (pin "1") (pinfunction "1_1") (pintype "passive"))
      (node (ref "IO2") (pin "4") (pinfunction "FB_4") (pintype "input"))
      (node (ref "TL2") (pin "2") (pinfunction "2_2") (pintype "passive"))
    )
    (net (code "60") (name "Net-(IO2-OUT)") (class "Default")
      (node (ref "D2") (pin "K") (pinfunction "K_K") (pintype "passive"))
      (node (ref "IO2") (pin "2") (pinfunction "OUT_2") (pintype "output"))
      (node (ref "TL2") (pin "1") (pinfunction "1_1") (pintype "passive"))
    )
    (net (code "61") (name "Net-(LED1-PadA)") (class "Default")
      (node (ref "LED1") (pin "A") (pinfunction "A_A") (pintype "passive"))
      (node (ref "R5") (pin "1") (pinfunction "1_1") (pintype "passive"))
    )
    (net (code "62") (name "Net-(MAIN_POWER-2-COM)") (class "Default")
      (node (ref "FUSE") (pin "1") (pinfunction "1_1") (pintype "passive"))
      (node (ref "MAIN_POWER") (pin "2") (pinfunction "2-COM_2") (pintype "passive"))
    )
    (net (code "63") (name "Net-(MOTOR-1-OFF)") (class "Default")
      (node (ref "FUSE3") (pin "2") (pinfunction "2_2") (pintype "passive"))
      (node (ref "MOTOR") (pin "1") (pinfunction "1-OFF_1") (pintype "passive"))
    )
    (net (code "64") (name "Net-(R4-Pad1)") (class "Default")
      (node (ref "R4") (pin "1") (pinfunction "1_1") (pintype "passive"))
      (node (ref "RPI_LED") (pin "A") (pinfunction "A_A") (pintype "passive"))
    )
    (net (code "65") (name "Net-(RESET_LINE_SISTEM-S)") (class "Default")
      (node (ref "C14") (pin "1") (pinfunction "1_1") (pintype "passive"))
      (node (ref "R2") (pin "1") (pinfunction "1_1") (pintype "passive"))
      (node (ref "RESET_LINE_SISTEM") (pin "1") (pinfunction "S_1") (pintype "passive"))
      (node (ref "RESET_LINE_SISTEM") (pin "2") (pinfunction "S1_2") (pintype "passive"))
      (node (ref "U2") (pin "29") (pinfunction "PC6(/RESET)_29") (pintype "bidirectional"))
    )
    (net (code "66") (name "Net-(U1-PB6(XTAL1{slash}TOSC1))") (class "Default")
      (node (ref "C2") (pin "2") (pinfunction "2_2") (pintype "passive"))
      (node (ref "U1") (pin "7") (pinfunction "PB6(XTAL1/TOSC1)_7") (pintype "bidirectional"))
      (node (ref "Y1") (pin "2") (pinfunction "2_2") (pintype "passive"))
    )
    (net (code "67") (name "Net-(U1-PB7(XTAL2{slash}TOSC2))") (class "Default")
      (node (ref "C1") (pin "2") (pinfunction "2_2") (pintype "passive"))
      (node (ref "U1") (pin "8") (pinfunction "PB7(XTAL2/TOSC2)_8") (pintype "bidirectional"))
      (node (ref "Y1") (pin "1") (pinfunction "1_1") (pintype "passive"))
    )
    (net (code "68") (name "Net-(U1-PC6({slash}RESET))") (class "Default")
      (node (ref "C3") (pin "1") (pinfunction "1_1") (pintype "passive"))
      (node (ref "R8") (pin "1") (pinfunction "1_1") (pintype "passive"))
      (node (ref "U1") (pin "29") (pinfunction "PC6(/RESET)_29") (pintype "bidirectional"))
      (node (ref "ULTRA_RESET") (pin "1") (pinfunction "S_1") (pintype "passive"))
      (node (ref "ULTRA_RESET") (pin "2") (pinfunction "S1_2") (pintype "passive"))
    )
    (net (code "69") (name "Net-(U1-PD0(RXD))") (class "Default")
      (node (ref "U1") (pin "30") (pinfunction "PD0(RXD)_30") (pintype "bidirectional"))
      (node (ref "ULTRA_SISTEM") (pin "3") (pinfunction "3_3") (pintype "passive"))
    )
    (net (code "70") (name "Net-(U1-PD1(TXD))") (class "Default")
      (node (ref "U1") (pin "31") (pinfunction "PD1(TXD)_31") (pintype "bidirectional"))
      (node (ref "ULTRA_SISTEM") (pin "2") (pinfunction "2_2") (pintype "passive"))
    )
    (net (code "71") (name "Net-(U2-PB6(XTAL1{slash}TOSC1))") (class "Default")
      (node (ref "C13") (pin "2") (pinfunction "2_2") (pintype "passive"))
      (node (ref "U2") (pin "7") (pinfunction "PB6(XTAL1/TOSC1)_7") (pintype "bidirectional"))
      (node (ref "Y2") (pin "2") (pinfunction "2_2") (pintype "passive"))
    )
    (net (code "72") (name "Net-(U2-PB7(XTAL2{slash}TOSC2))") (class "Default")
      (node (ref "C12") (pin "2") (pinfunction "2_2") (pintype "passive"))
      (node (ref "U2") (pin "8") (pinfunction "PB7(XTAL2/TOSC2)_8") (pintype "bidirectional"))
      (node (ref "Y2") (pin "1") (pinfunction "1_1") (pintype "passive"))
    )
    (net (code "73") (name "unconnected-(BATERY_1-Pad1)") (class "Default")
      (node (ref "BATERY_1") (pin "1") (pinfunction "1_1") (pintype "bidirectional"))
    )
    (net (code "74") (name "unconnected-(BATERY_1-Pad2)") (class "Default")
      (node (ref "BATERY_1") (pin "2") (pinfunction "2_2") (pintype "bidirectional"))
    )
    (net (code "75") (name "unconnected-(BATERY_1-Pad4)") (class "Default")
      (node (ref "BATERY_1") (pin "4") (pinfunction "4_4") (pintype "bidirectional"))
    )
    (net (code "76") (name "unconnected-(BATERY_2-Pad1)") (class "Default")
      (node (ref "BATERY_2") (pin "1") (pinfunction "1_1") (pintype "bidirectional"))
    )
    (net (code "77") (name "unconnected-(BATERY_2-Pad2)") (class "Default")
      (node (ref "BATERY_2") (pin "2") (pinfunction "2_2") (pintype "bidirectional"))
    )
    (net (code "78") (name "unconnected-(BATERY_2-Pad4)") (class "Default")
      (node (ref "BATERY_2") (pin "4") (pinfunction "4_4") (pintype "bidirectional"))
    )
    (net (code "79") (name "unconnected-(BATERY_3-Pad1)") (class "Default")
      (node (ref "BATERY_3") (pin "1") (pinfunction "1_1") (pintype "bidirectional"))
    )
    (net (code "80") (name "unconnected-(BATERY_3-Pad2)") (class "Default")
      (node (ref "BATERY_3") (pin "2") (pinfunction "2_2") (pintype "bidirectional"))
    )
    (net (code "81") (name "unconnected-(BATERY_3-Pad4)") (class "Default")
      (node (ref "BATERY_3") (pin "4") (pinfunction "4_4") (pintype "bidirectional"))
    )
    (net (code "82") (name "unconnected-(JP8-Pad10)") (class "Default")
      (node (ref "JP8") (pin "10") (pinfunction "10_10") (pintype "passive"))
    )
    (net (code "83") (name "unconnected-(KICKER-Pad5)") (class "Default")
      (node (ref "KICKER") (pin "5") (pinfunction "5_5") (pintype "passive"))
    )
    (net (code "84") (name "unconnected-(LINE_SISTEM-Pad5)") (class "Default")
      (node (ref "LINE_SISTEM") (pin "5") (pinfunction "5_5") (pintype "passive"))
    )
    (net (code "85") (name "unconnected-(MAIN_POWER-3-ON-Pad3)") (class "Default")
      (node (ref "MAIN_POWER") (pin "3") (pinfunction "3-ON_3") (pintype "passive"))
    )
    (net (code "86") (name "unconnected-(MOTOR-3-ON-Pad3)") (class "Default")
      (node (ref "MOTOR") (pin "3") (pinfunction "3-ON_3") (pintype "passive"))
    )
    (net (code "87") (name "unconnected-(SMALL_LINE-Pad5)") (class "Default")
      (node (ref "SMALL_LINE") (pin "5") (pinfunction "5_5") (pintype "passive"))
    )
    (net (code "88") (name "unconnected-(U$4-PadCS)") (class "Default")
      (node (ref "U$4") (pin "CS") (pinfunction "CS_CS") (pintype "bidirectional"))
    )
    (net (code "89") (name "unconnected-(U$4-PadENA{slash}DIAGA)") (class "Default")
      (node (ref "U$4") (pin "ENA/DIAGA") (pinfunction "ENA/DIAGA_ENA/DIAGA") (pintype "bidirectional"))
    )
    (net (code "90") (name "unconnected-(U$4-PadENB{slash}DIAGB)") (class "Default")
      (node (ref "U$4") (pin "ENB/DIAGB") (pinfunction "ENB/DIAGB_ENB/DIAGB") (pintype "bidirectional"))
    )
    (net (code "91") (name "unconnected-(U$4-PadVOUT)") (class "Default")
      (node (ref "U$4") (pin "VOUT") (pinfunction "VOUT_VOUT") (pintype "bidirectional"))
    )
    (net (code "92") (name "unconnected-(U1-ADC6-Pad19)") (class "Default")
      (node (ref "U1") (pin "19") (pinfunction "ADC6_19") (pintype "bidirectional"))
    )
    (net (code "93") (name "unconnected-(U1-ADC7-Pad22)") (class "Default")
      (node (ref "U1") (pin "22") (pinfunction "ADC7_22") (pintype "bidirectional"))
    )
    (net (code "94") (name "unconnected-(U1-AREF-Pad20)") (class "Default")
      (node (ref "U1") (pin "20") (pinfunction "AREF_20") (pintype "bidirectional"))
    )
    (net (code "95") (name "unconnected-(U1-PB0(ICP)-Pad12)") (class "Default")
      (node (ref "U1") (pin "12") (pinfunction "PB0(ICP)_12") (pintype "bidirectional"))
    )
    (net (code "96") (name "unconnected-(U1-PB1(OC1A)-Pad13)") (class "Default")
      (node (ref "U1") (pin "13") (pinfunction "PB1(OC1A)_13") (pintype "bidirectional"))
    )
    (net (code "97") (name "unconnected-(U1-PC0(ADC0)-Pad23)") (class "Default")
      (node (ref "U1") (pin "23") (pinfunction "PC0(ADC0)_23") (pintype "bidirectional"))
    )
    (net (code "98") (name "unconnected-(U1-PC1(ADC1)-Pad24)") (class "Default")
      (node (ref "U1") (pin "24") (pinfunction "PC1(ADC1)_24") (pintype "bidirectional"))
    )
    (net (code "99") (name "unconnected-(U1-PC2(ADC2)-Pad25)") (class "Default")
      (node (ref "U1") (pin "25") (pinfunction "PC2(ADC2)_25") (pintype "bidirectional"))
    )
    (net (code "100") (name "unconnected-(U1-PC3(ADC3)-Pad26)") (class "Default")
      (node (ref "U1") (pin "26") (pinfunction "PC3(ADC3)_26") (pintype "bidirectional"))
    )
    (net (code "101") (name "unconnected-(U1-PC4(ADC4{slash}SDA)-Pad27)") (class "Default")
      (node (ref "U1") (pin "27") (pinfunction "PC4(ADC4/SDA)_27") (pintype "bidirectional"))
    )
    (net (code "102") (name "unconnected-(U1-PC5(ADC5{slash}SCL)-Pad28)") (class "Default")
      (node (ref "U1") (pin "28") (pinfunction "PC5(ADC5/SCL)_28") (pintype "bidirectional"))
    )
    (net (code "103") (name "unconnected-(U1-PD2(INT0)-Pad32)") (class "Default")
      (node (ref "U1") (pin "32") (pinfunction "PD2(INT0)_32") (pintype "bidirectional"))
    )
    (net (code "104") (name "unconnected-(U1-PD3(INT1)-Pad1)") (class "Default")
      (node (ref "U1") (pin "1") (pinfunction "PD3(INT1)_1") (pintype "bidirectional"))
    )
    (net (code "105") (name "unconnected-(U1-PD4(XCK{slash}T0)-Pad2)") (class "Default")
      (node (ref "U1") (pin "2") (pinfunction "PD4(XCK/T0)_2") (pintype "bidirectional"))
    )
    (net (code "106") (name "unconnected-(U2-ADC6-Pad19)") (class "Default")
      (node (ref "U2") (pin "19") (pinfunction "ADC6_19") (pintype "bidirectional"))
    )
    (net (code "107") (name "unconnected-(U2-ADC7-Pad22)") (class "Default")
      (node (ref "U2") (pin "22") (pinfunction "ADC7_22") (pintype "bidirectional"))
    )
    (net (code "108") (name "unconnected-(U2-AREF-Pad20)") (class "Default")
      (node (ref "U2") (pin "20") (pinfunction "AREF_20") (pintype "bidirectional"))
    )
    (net (code "109") (name "unconnected-(U2-PC1(ADC1)-Pad24)") (class "Default")
      (node (ref "U2") (pin "24") (pinfunction "PC1(ADC1)_24") (pintype "bidirectional"))
    )
    (net (code "110") (name "unconnected-(U2-PC2(ADC2)-Pad25)") (class "Default")
      (node (ref "U2") (pin "25") (pinfunction "PC2(ADC2)_25") (pintype "bidirectional"))
    )
    (net (code "111") (name "unconnected-(U2-PC3(ADC3)-Pad26)") (class "Default")
      (node (ref "U2") (pin "26") (pinfunction "PC3(ADC3)_26") (pintype "bidirectional"))
    )
    (net (code "112") (name "unconnected-(ULTRA_SISTEM-Pad5)") (class "Default")
      (node (ref "ULTRA_SISTEM") (pin "5") (pinfunction "5_5") (pintype "passive"))
    )
  )
)
